# xboxeeprombeforearoute-2.net
KiCad netlist of a schematic drawn in EAGLE
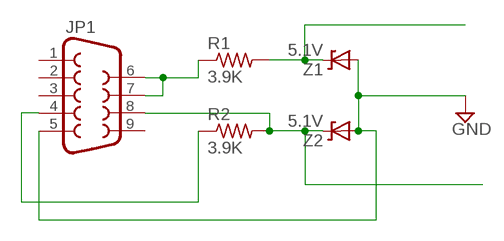
[diagram p0: schematic, sheet 1]

(export (version "E")
  (design (tool "Eeschema 10.0.6"))
  (components
    (comp (ref "JP1")
      (value "DB9FEMALE")
      (footprint "eagle-import:DB9")
      (libsource (lib "eagle-import") (part "DB9FEMALE"))
    )
    (comp (ref "R1")
      (value "3.9K")
      (footprint "eagle-import:0207_9")
      (libsource (lib "eagle-import") (part "R-US_0207/9"))
    )
    (comp (ref "R2")
      (value "3.9K")
      (footprint "eagle-import:0207_9")
      (libsource (lib "eagle-import") (part "R-US_0207/9"))
    )
    (comp (ref "Z1")
      (value "5.1V")
      (footprint "eagle-import:DIODE-ZENER")
      (libsource (lib "eagle-import") (part "DIODE-ZENERPTH"))
    )
    (comp (ref "Z2")
      (value "5.1V")
      (footprint "eagle-import:DIODE-ZENER")
      (libsource (lib "eagle-import") (part "DIODE-ZENERPTH"))
    )
  )
  (nets
    (net (code "1") (name "GND") (class "Default")
      (node (ref "JP1") (pin "5") (pinfunction "5_5") (pintype "passive"))
      (node (ref "Z1") (pin "P$2") (pinfunction "A_P$2") (pintype "passive"))
      (node (ref "Z2") (pin "P$2") (pinfunction "A_P$2") (pintype "passive"))
    )
    (net (code "2") (name "Net-(JP1-Pad4)") (class "Default")
      (node (ref "JP1") (pin "4") (pinfunction "4_4") (pintype "passive"))
      (node (ref "R2") (pin "1") (pinfunction "1_1") (pintype "passive"))
    )
    (net (code "3") (name "Net-(JP1-Pad6)") (class "Default")
      (node (ref "JP1") (pin "6") (pinfunction "6_6") (pintype "passive"))
      (node (ref "JP1") (pin "7") (pinfunction "7_7") (pintype "passive"))
      (node (ref "R1") (pin "1") (pinfunction "1_1") (pintype "passive"))
    )
    (net (code "4") (name "Net-(Z1-C)") (class "Default")
      (node (ref "R1") (pin "2") (pinfunction "2_2") (pintype "passive"))
      (node (ref "Z1") (pin "P$1") (pinfunction "C_P$1") (pintype "passive"))
    )
    (net (code "5") (name "Net-(Z2-C)") (class "Default")
      (node (ref "JP1") (pin "8") (pinfunction "8_8") (pintype "passive"))
      (node (ref "R2") (pin "2") (pinfunction "2_2") (pintype "passive"))
      (node (ref "Z2") (pin "P$1") (pinfunction "C_P$1") (pintype "passive"))
    )
    (net (code "6") (name "unconnected-(JP1-Pad1)") (class "Default")
      (node (ref "JP1") (pin "1") (pinfunction "1_1") (pintype "passive"))
    )
    (net (code "7") (name "unconnected-(JP1-Pad2)") (class "Default")
      (node (ref "JP1") (pin "2") (pinfunction "2_2") (pintype "passive"))
    )
    (net (code "8") (name "unconnected-(JP1-Pad3)") (class "Default")
      (node (ref "JP1") (pin "3") (pinfunction "3_3") (pintype "passive"))
    )
    (net (code "9") (name "unconnected-(JP1-Pad9)") (class "Default")
      (node (ref "JP1") (pin "9") (pinfunction "9_9") (pintype "passive"))
    )
  )
)
